# SCH_Thermostat-mk2.net
KiCad netlist of a schematic drawn in EasyEDA
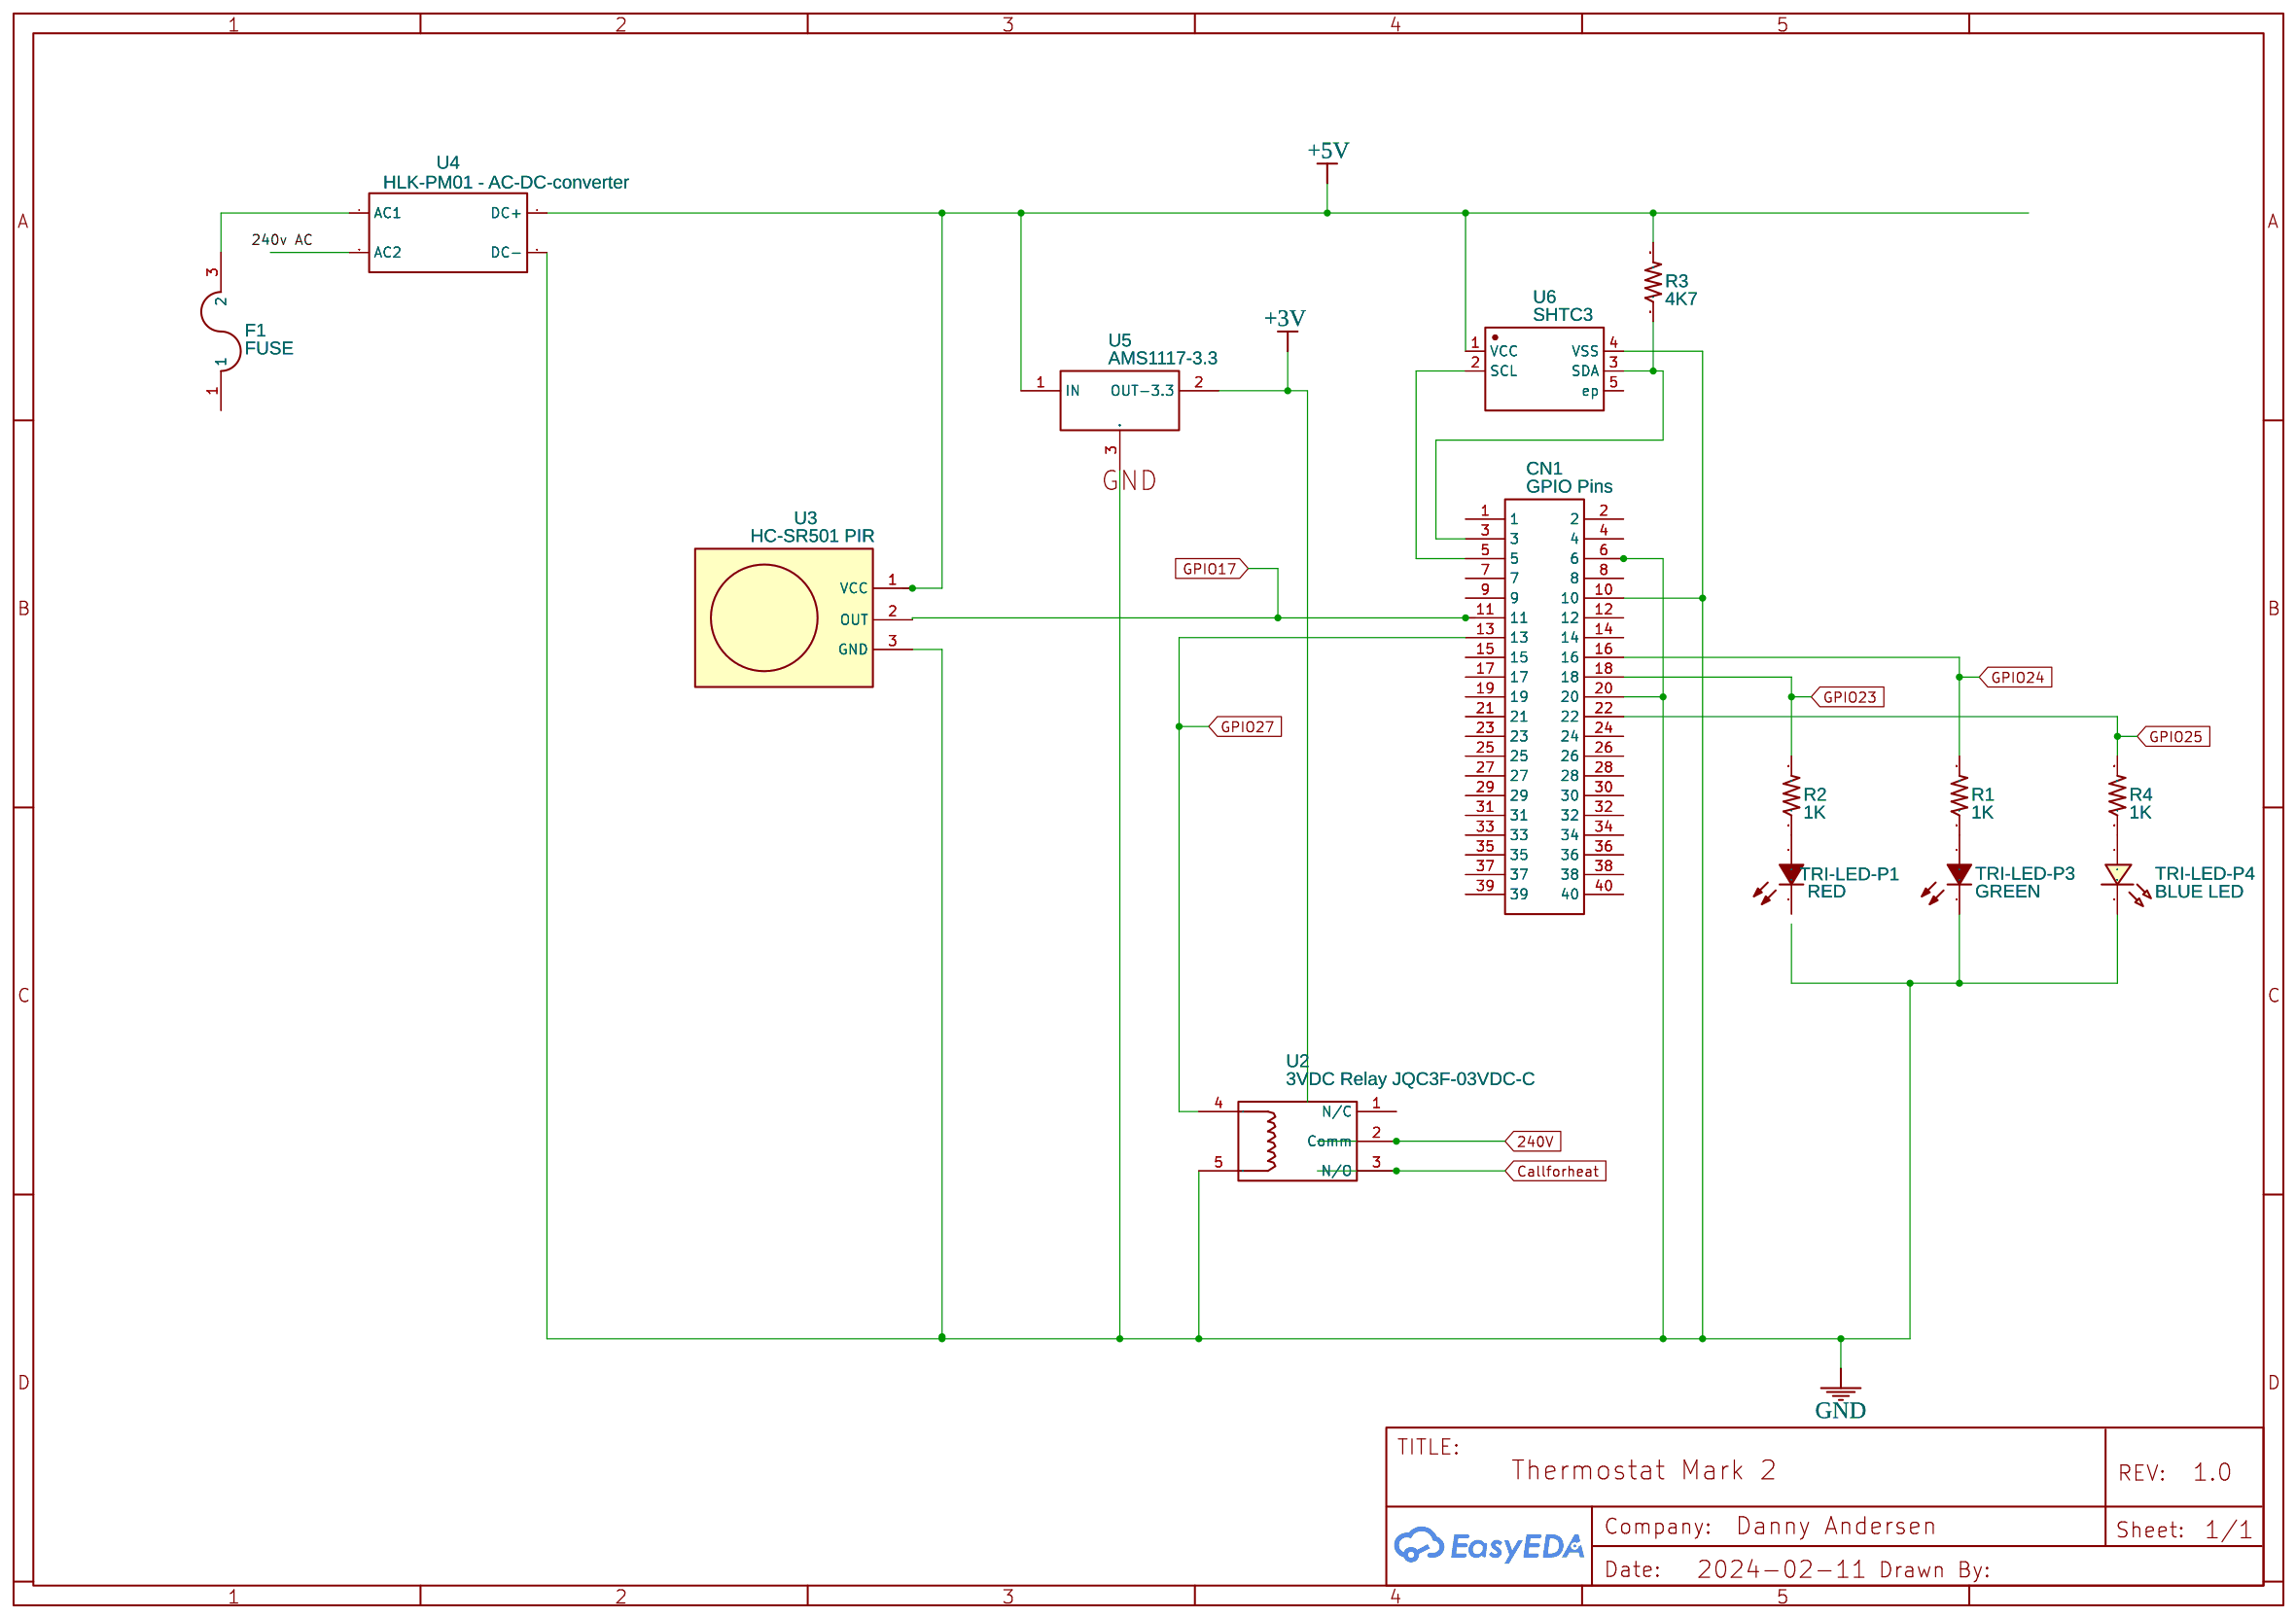
[diagram p0: schematic sheet]

(export (version "E")
  (design (tool "Eeschema 10.0.6"))
  (components
    (comp (ref "CN1")
      (value "GPIO Pins")
      (fields
        (field (name "Manufacturer Part") "2.54-2*20P压线头")
        (field (name "Manufacturer") "BOOMELE(博穆精密)")
      )
      (libsource (lib "") (part "Crimping terminals2*20"))
    )
    (comp (ref "F1")
      (value "FUSE")
      (fields (field (name "Manufacturer Part") "?"))
      (libsource (lib "") (part "Unknown_105_-645"))
    )
    (comp (ref "R1")
      (value "1K")
      (fields (field (name "Manufacturer Part") "?"))
      (libsource (lib "") (part "Unknown_985_-410"))
    )
    (comp (ref "R2")
      (value "1K")
      (fields (field (name "Manufacturer Part") "?"))
      (libsource (lib "") (part "Unknown_900_-410"))
    )
    (comp (ref "R3")
      (value "4K7")
      (fields (field (name "Manufacturer Part") "?"))
      (libsource (lib "") (part "Unknown_830_-670"))
    )
    (comp (ref "R4")
      (value "1K")
      (fields (field (name "Manufacturer Part") "?"))
      (libsource (lib "") (part "Unknown_1065_-410"))
    )
    (comp (ref "TRI-LED-P1")
      (value "RED")
      (fields (field (name "Manufacturer Part") "5600") (field (name "Manufacturer") "VccLite"))
      (libsource (lib "") (part "LED"))
    )
    (comp (ref "TRI-LED-P3")
      (value "GREEN")
      (fields (field (name "Manufacturer Part") "5600") (field (name "Manufacturer") "VccLite"))
      (libsource (lib "") (part "LED"))
    )
    (comp (ref "TRI-LED-P4")
      (value "BLUE LED")
      (fields
        (field (name "Manufacturer Part") "19-217/R6C-AL1M2VY/3T")
        (field (name "Manufacturer") "EVERLIGHT(台湾亿光)")
      )
      (libsource (lib "") (part "LED-0603_R"))
    )
    (comp (ref "U2")
      (value "3VDC Relay JQC3F-03VDC-C")
      (libsource (lib "") (part "3VDC Relay JQC3F-03VDC-C"))
    )
    (comp (ref "U3")
      (value "HC-SR501 PIR")
      (fields (field (name "Manufacturer Part") "?"))
      (libsource (lib "") (part "Unknown_345_-465"))
    )
    (comp (ref "U4")
      (value "HLK-PM01 - AC-DC-converter")
      (fields (field (name "Manufacturer Part") "?"))
      (libsource (lib "") (part "Unknown_210_-695"))
    )
    (comp (ref "U5")
      (value "AMS1117-3.3")
      (fields (field (name "Manufacturer Part") "CJ78L05") (field (name "Manufacturer") "CJ"))
      (libsource (lib "") (part "7805(SOT-89)"))
    )
    (comp (ref "U6")
      (value "SHTC3")
      (fields
        (field (name "Manufacturer Part") "SHTC3-TR-2.5KS")
        (field (name "Manufacturer") "Sensirion(瑞士盛思锐)")
      )
      (libsource (lib "") (part "SHTC3"))
    )
  )
  (nets
    (net (code "1") (name "+3V") (class "Default")
      (node (ref "U5") (pin "2") (pinfunction "OUT-3.3_2") (pintype "passive"))
    )
    (net (code "2") (name "+5V") (class "Default")
      (node (ref "R3") (pin "P$2") (pinfunction "2_P$2") (pintype "unspecified"))
      (node (ref "U3") (pin "1") (pinfunction "VCC_1") (pintype "unspecified"))
      (node (ref "U4") (pin "4") (pinfunction "DC+_4") (pintype "unspecified"))
      (node (ref "U5") (pin "1") (pinfunction "IN_1") (pintype "passive"))
      (node (ref "U6") (pin "1") (pinfunction "VCC_1") (pintype "unspecified"))
    )
    (net (code "4") (name "240V") (class "Default")
      (node (ref "U2") (pin "2") (pinfunction "Comm_2") (pintype "unspecified"))
    )
    (net (code "5") (name "Callforheat") (class "Default")
      (node (ref "U2") (pin "3") (pinfunction "N/O_3") (pintype "unspecified"))
    )
    (net (code "6") (name "GND") (class "Default")
      (node (ref "CN1") (pin "10") (pinfunction "10_10") (pintype "unspecified"))
      (node (ref "CN1") (pin "20") (pinfunction "20_20") (pintype "unspecified"))
      (node (ref "CN1") (pin "6") (pinfunction "6_6") (pintype "unspecified"))
      (node (ref "TRI-LED-P3") (pin "2") (pinfunction "K_2") (pintype "unspecified"))
      (node (ref "TRI-LED-P4") (pin "2") (pinfunction "2_2") (pintype "unspecified"))
      (node (ref "U2") (pin "5") (pinfunction "5_5") (pintype "unspecified"))
      (node (ref "U3") (pin "3") (pinfunction "GND_3") (pintype "unspecified"))
      (node (ref "U4") (pin "3") (pinfunction "DC-_3") (pintype "unspecified"))
      (node (ref "U5") (pin "3") (pinfunction "GND_3") (pintype "passive"))
      (node (ref "U6") (pin "4") (pinfunction "VSS_4") (pintype "unspecified"))
    )
    (net (code "7") (name "GPIO17") (class "Default")
      (node (ref "CN1") (pin "11") (pinfunction "11_11") (pintype "unspecified"))
      (node (ref "U3") (pin "2") (pinfunction "OUT_2") (pintype "unspecified"))
    )
    (net (code "8") (name "GPIO23") (class "Default")
      (node (ref "CN1") (pin "18") (pinfunction "18_18") (pintype "unspecified"))
      (node (ref "R2") (pin "P$2") (pinfunction "2_P$2") (pintype "unspecified"))
    )
    (net (code "9") (name "GPIO24") (class "Default")
      (node (ref "CN1") (pin "16") (pinfunction "16_16") (pintype "unspecified"))
      (node (ref "R1") (pin "P$2") (pinfunction "2_P$2") (pintype "unspecified"))
    )
    (net (code "10") (name "GPIO25") (class "Default")
      (node (ref "CN1") (pin "22") (pinfunction "22_22") (pintype "unspecified"))
      (node (ref "R4") (pin "P$2") (pinfunction "2_P$2") (pintype "unspecified"))
    )
    (net (code "11") (name "GPIO27") (class "Default")
      (node (ref "CN1") (pin "13") (pinfunction "13_13") (pintype "unspecified"))
      (node (ref "U2") (pin "4") (pinfunction "4_4") (pintype "unspecified"))
    )
    (net (code "12") (name "Net-(F1-2)") (class "Default")
      (node (ref "F1") (pin "3") (pinfunction "2_3") (pintype "unspecified"))
      (node (ref "U4") (pin "1") (pinfunction "AC1_1") (pintype "input"))
    )
    (net (code "13") (name "Net-(R1-1)") (class "Default")
      (node (ref "R1") (pin "P$1") (pinfunction "1_P$1") (pintype "unspecified"))
      (node (ref "TRI-LED-P3") (pin "1") (pinfunction "A_1") (pintype "unspecified"))
    )
    (net (code "14") (name "Net-(R2-1)") (class "Default")
      (node (ref "R2") (pin "P$1") (pinfunction "1_P$1") (pintype "unspecified"))
      (node (ref "TRI-LED-P1") (pin "1") (pinfunction "A_1") (pintype "unspecified"))
    )
    (net (code "15") (name "Net-(R3-1)") (class "Default")
      (node (ref "CN1") (pin "3") (pinfunction "3_3") (pintype "unspecified"))
      (node (ref "R3") (pin "P$1") (pinfunction "1_P$1") (pintype "unspecified"))
      (node (ref "U6") (pin "3") (pinfunction "SDA_3") (pintype "unspecified"))
    )
    (net (code "16") (name "Net-(R4-1)") (class "Default")
      (node (ref "R4") (pin "P$1") (pinfunction "1_P$1") (pintype "unspecified"))
      (node (ref "TRI-LED-P4") (pin "1") (pinfunction "1_1") (pintype "unspecified"))
    )
    (net (code "17") (name "Net-(U6-SCL)") (class "Default")
      (node (ref "CN1") (pin "5") (pinfunction "5_5") (pintype "unspecified"))
      (node (ref "U6") (pin "2") (pinfunction "SCL_2") (pintype "unspecified"))
    )
    (net (code "18") (name "unconnected-(CN1-Pad1)") (class "Default")
      (node (ref "CN1") (pin "1") (pinfunction "1_1") (pintype "unspecified"))
    )
    (net (code "19") (name "unconnected-(CN1-Pad2)") (class "Default")
      (node (ref "CN1") (pin "2") (pinfunction "2_2") (pintype "unspecified"))
    )
    (net (code "20") (name "unconnected-(CN1-Pad4)") (class "Default")
      (node (ref "CN1") (pin "4") (pinfunction "4_4") (pintype "unspecified"))
    )
    (net (code "21") (name "unconnected-(CN1-Pad7)") (class "Default")
      (node (ref "CN1") (pin "7") (pinfunction "7_7") (pintype "unspecified"))
    )
    (net (code "22") (name "unconnected-(CN1-Pad8)") (class "Default")
      (node (ref "CN1") (pin "8") (pinfunction "8_8") (pintype "unspecified"))
    )
    (net (code "23") (name "unconnected-(CN1-Pad9)") (class "Default")
      (node (ref "CN1") (pin "9") (pinfunction "9_9") (pintype "unspecified"))
    )
    (net (code "24") (name "unconnected-(CN1-Pad12)") (class "Default")
      (node (ref "CN1") (pin "12") (pinfunction "12_12") (pintype "unspecified"))
    )
    (net (code "25") (name "unconnected-(CN1-Pad14)") (class "Default")
      (node (ref "CN1") (pin "14") (pinfunction "14_14") (pintype "unspecified"))
    )
    (net (code "26") (name "unconnected-(CN1-Pad15)") (class "Default")
      (node (ref "CN1") (pin "15") (pinfunction "15_15") (pintype "unspecified"))
    )
    (net (code "27") (name "unconnected-(CN1-Pad17)") (class "Default")
      (node (ref "CN1") (pin "17") (pinfunction "17_17") (pintype "unspecified"))
    )
    (net (code "28") (name "unconnected-(CN1-Pad19)") (class "Default")
      (node (ref "CN1") (pin "19") (pinfunction "19_19") (pintype "unspecified"))
    )
    (net (code "29") (name "unconnected-(CN1-Pad21)") (class "Default")
      (node (ref "CN1") (pin "21") (pinfunction "21_21") (pintype "unspecified"))
    )
    (net (code "30") (name "unconnected-(CN1-Pad23)") (class "Default")
      (node (ref "CN1") (pin "23") (pinfunction "23_23") (pintype "unspecified"))
    )
    (net (code "31") (name "unconnected-(CN1-Pad24)") (class "Default")
      (node (ref "CN1") (pin "24") (pinfunction "24_24") (pintype "unspecified"))
    )
    (net (code "32") (name "unconnected-(CN1-Pad25)") (class "Default")
      (node (ref "CN1") (pin "25") (pinfunction "25_25") (pintype "unspecified"))
    )
    (net (code "33") (name "unconnected-(CN1-Pad26)") (class "Default")
      (node (ref "CN1") (pin "26") (pinfunction "26_26") (pintype "unspecified"))
    )
    (net (code "34") (name "unconnected-(CN1-Pad27)") (class "Default")
      (node (ref "CN1") (pin "27") (pinfunction "27_27") (pintype "unspecified"))
    )
    (net (code "35") (name "unconnected-(CN1-Pad28)") (class "Default")
      (node (ref "CN1") (pin "28") (pinfunction "28_28") (pintype "unspecified"))
    )
    (net (code "36") (name "unconnected-(CN1-Pad29)") (class "Default")
      (node (ref "CN1") (pin "29") (pinfunction "29_29") (pintype "unspecified"))
    )
    (net (code "37") (name "unconnected-(CN1-Pad30)") (class "Default")
      (node (ref "CN1") (pin "30") (pinfunction "30_30") (pintype "unspecified"))
    )
    (net (code "38") (name "unconnected-(CN1-Pad31)") (class "Default")
      (node (ref "CN1") (pin "31") (pinfunction "31_31") (pintype "unspecified"))
    )
    (net (code "39") (name "unconnected-(CN1-Pad32)") (class "Default")
      (node (ref "CN1") (pin "32") (pinfunction "32_32") (pintype "unspecified"))
    )
    (net (code "40") (name "unconnected-(CN1-Pad33)") (class "Default")
      (node (ref "CN1") (pin "33") (pinfunction "33_33") (pintype "unspecified"))
    )
    (net (code "41") (name "unconnected-(CN1-Pad34)") (class "Default")
      (node (ref "CN1") (pin "34") (pinfunction "34_34") (pintype "unspecified"))
    )
    (net (code "42") (name "unconnected-(CN1-Pad35)") (class "Default")
      (node (ref "CN1") (pin "35") (pinfunction "35_35") (pintype "unspecified"))
    )
    (net (code "43") (name "unconnected-(CN1-Pad36)") (class "Default")
      (node (ref "CN1") (pin "36") (pinfunction "36_36") (pintype "unspecified"))
    )
    (net (code "44") (name "unconnected-(CN1-Pad37)") (class "Default")
      (node (ref "CN1") (pin "37") (pinfunction "37_37") (pintype "unspecified"))
    )
    (net (code "45") (name "unconnected-(CN1-Pad38)") (class "Default")
      (node (ref "CN1") (pin "38") (pinfunction "38_38") (pintype "unspecified"))
    )
    (net (code "46") (name "unconnected-(CN1-Pad39)") (class "Default")
      (node (ref "CN1") (pin "39") (pinfunction "39_39") (pintype "unspecified"))
    )
    (net (code "47") (name "unconnected-(CN1-Pad40)") (class "Default")
      (node (ref "CN1") (pin "40") (pinfunction "40_40") (pintype "unspecified"))
    )
    (net (code "48") (name "unconnected-(F1-Pad1)") (class "Default")
      (node (ref "F1") (pin "1") (pinfunction "1_1") (pintype "unspecified"))
    )
    (net (code "49") (name "unconnected-(TRI-LED-P1-K-Pad2)") (class "Default")
      (node (ref "TRI-LED-P1") (pin "2") (pinfunction "K_2") (pintype "unspecified"))
    )
    (net (code "50") (name "unconnected-(U2-N{slash}C-Pad1)") (class "Default")
      (node (ref "U2") (pin "1") (pinfunction "N/C_1") (pintype "unspecified"))
    )
    (net (code "51") (name "unconnected-(U4-AC2-Pad2)") (class "Default")
      (node (ref "U4") (pin "2") (pinfunction "AC2_2") (pintype "input"))
    )
    (net (code "52") (name "unconnected-(U6-ep-Pad5)") (class "Default")
      (node (ref "U6") (pin "5") (pinfunction "ep_5") (pintype "unspecified"))
    )
  )
)
